# IMU.net
KiCad netlist of a schematic drawn in Altium Designer
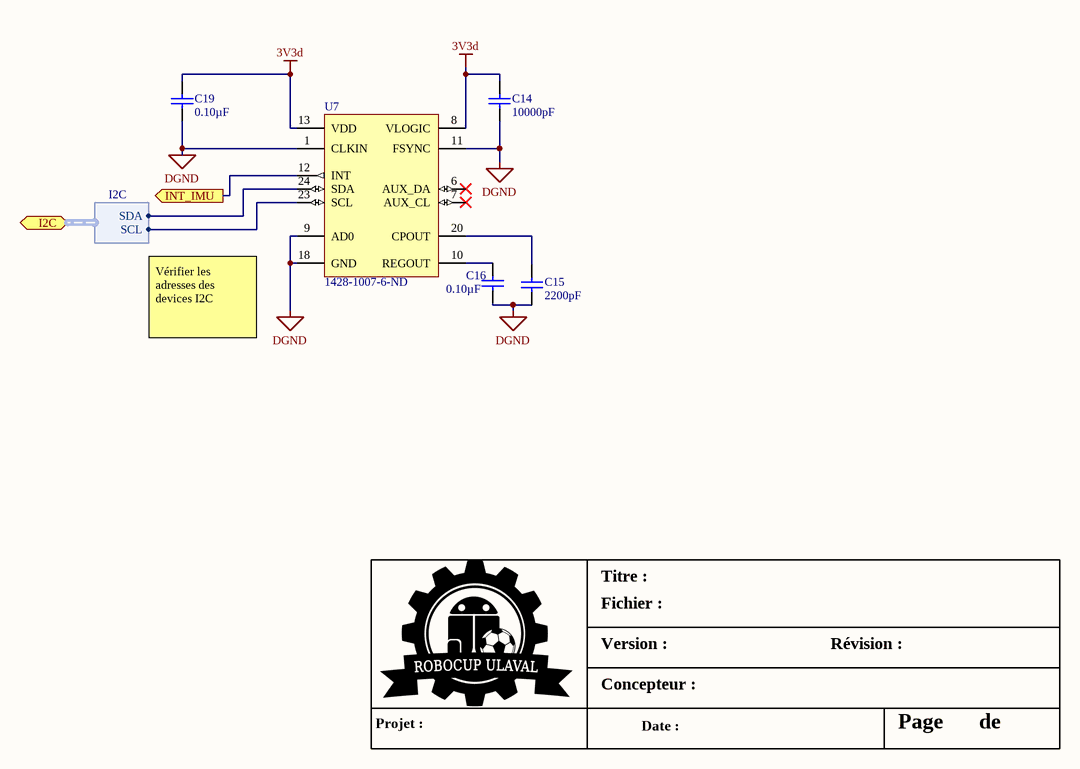
[diagram p0: IMU.SchDoc]

(export (version "E")
  (design (tool "Eeschema 10.0.6"))
  (components
    (comp (ref "C14")
      (value "GRM188R71H103KA01D")
      (footprint "0603")
      (description "CAP CER 10000PF 50V X7R 0603")
      (fields
        (field (name "MANUFACTURER") "Murata Electronics North America")
        (field (name "TOLERANCE") "±10%")
        (field (name "CAPACITANCE") "10000pF")
      )
      (libsource (lib "ResCap") (part "GRM188R71H103KA01D"))
    )
    (comp (ref "C15")
      (value "CL10B222KB8SFNC")
      (footprint "0603")
      (description "CAP CER 2200PF 50V X7R 0603")
      (fields
        (field (name "MANUFACTURER") "Samsung Electro-Mechanics America, Inc.")
        (field (name "TOLERANCE") "±10%")
        (field (name "CAPACITANCE") "2200pF")
      )
      (libsource (lib "ResCap") (part "CL10B222KB8SFNC"))
    )
    (comp (ref "C16")
      (value "CL10B104KB8SFNC")
      (footprint "0603")
      (description "CAP CER 0.1UF 50V X7R 0603")
      (fields
        (field (name "MANUFACTURER") "Samsung Electro-Mechanics America, Inc.")
        (field (name "TOLERANCE") "±10%")
        (field (name "CAPACITANCE") "0.10µF")
      )
      (libsource (lib "ResCap") (part "CL10B104KB8SFNC"))
    )
    (comp (ref "C19")
      (value "CL10B104KB8SFNC")
      (footprint "0603")
      (description "CAP CER 0.1UF 50V X7R 0603")
      (fields
        (field (name "MANUFACTURER") "Samsung Electro-Mechanics America, Inc.")
        (field (name "TOLERANCE") "±10%")
        (field (name "CAPACITANCE") "0.10µF")
      )
      (libsource (lib "ResCap") (part "CL10B104KB8SFNC"))
    )
    (comp (ref "U7")
      (value "MPU-6050")
      (footprint "VQFN-24")
      (description "GYRO/ACCELEROMETER 6AXIS 24QFN")
      (fields
        (field (name "MANUFACTURER") "InvenSense")
        (field (name "SUPPLIER PART NUMBER 1") "1428-1007-6-ND")
      )
      (libsource (lib "MainBoard") (part "MPU-6050"))
    )
  )
  (nets
    (net (code "2") (name "/INT_IMU") (class "Default")
      (node (ref "U7") (pin "12") (pinfunction "INT_12") (pintype "output"))
    )
    (net (code "3") (name "/SCL") (class "Default")
      (node (ref "U7") (pin "23") (pinfunction "SCL_23") (pintype "bidirectional"))
    )
    (net (code "4") (name "/SDA") (class "Default")
      (node (ref "U7") (pin "24") (pinfunction "SDA_24") (pintype "bidirectional"))
    )
    (net (code "6") (name "3V3d") (class "Default")
      (node (ref "C14") (pin "2") (pinfunction "2_2") (pintype "passive"))
      (node (ref "C19") (pin "2") (pinfunction "2_2") (pintype "passive"))
      (node (ref "U7") (pin "13") (pinfunction "VDD_13") (pintype "power_in"))
      (node (ref "U7") (pin "8") (pinfunction "VLOGIC_8") (pintype "power_in"))
    )
    (net (code "7") (name "DGND") (class "Default")
      (node (ref "C14") (pin "1") (pinfunction "1_1") (pintype "passive"))
      (node (ref "C15") (pin "1") (pinfunction "1_1") (pintype "passive"))
      (node (ref "C16") (pin "1") (pinfunction "1_1") (pintype "passive"))
      (node (ref "C19") (pin "1") (pinfunction "1_1") (pintype "passive"))
      (node (ref "U7") (pin "1") (pinfunction "CLKIN_1") (pintype "passive"))
      (node (ref "U7") (pin "11") (pinfunction "FSYNC_11") (pintype "passive"))
      (node (ref "U7") (pin "18") (pinfunction "GND_18") (pintype "power_in"))
      (node (ref "U7") (pin "9") (pinfunction "AD0_9") (pintype "passive"))
    )
    (net (code "8") (name "Net-(U7-CPOUT)") (class "Default")
      (node (ref "C15") (pin "2") (pinfunction "2_2") (pintype "passive"))
      (node (ref "U7") (pin "20") (pinfunction "CPOUT_20") (pintype "passive"))
    )
    (net (code "9") (name "Net-(U7-REGOUT)") (class "Default")
      (node (ref "C16") (pin "2") (pinfunction "2_2") (pintype "passive"))
      (node (ref "U7") (pin "10") (pinfunction "REGOUT_10") (pintype "passive"))
    )
    (net (code "10") (name "unconnected-(U7-AUX_CL-Pad7)") (class "Default")
      (node (ref "U7") (pin "7") (pinfunction "AUX_CL_7") (pintype "bidirectional+no_connect"))
    )
    (net (code "11") (name "unconnected-(U7-AUX_DA-Pad6)") (class "Default")
      (node (ref "U7") (pin "6") (pinfunction "AUX_DA_6") (pintype "bidirectional+no_connect"))
    )
  )
)
